# URC-ESP32.net
KiCad netlist of a schematic drawn in EAGLE
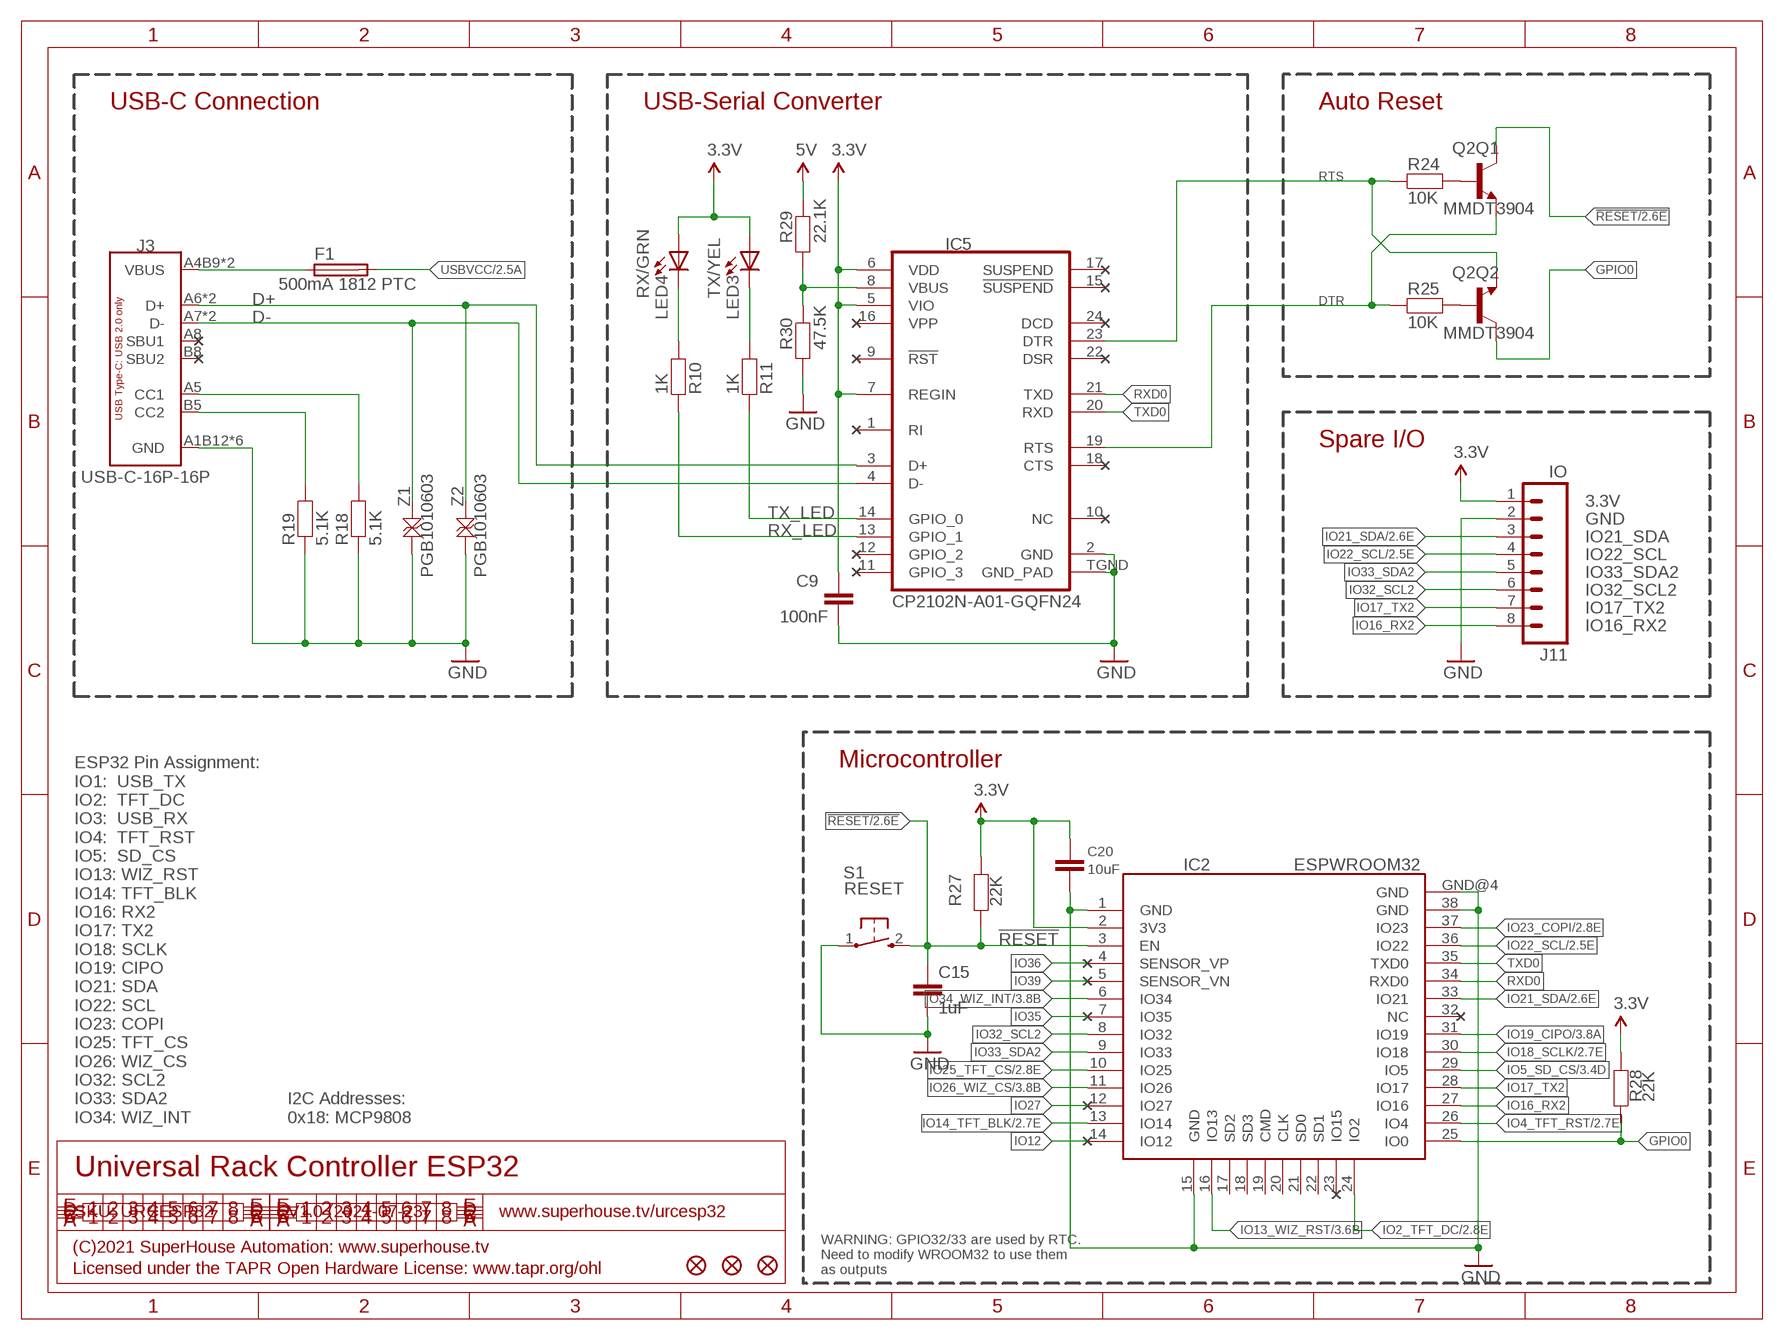
[diagram p0: schematic, sheet 1]
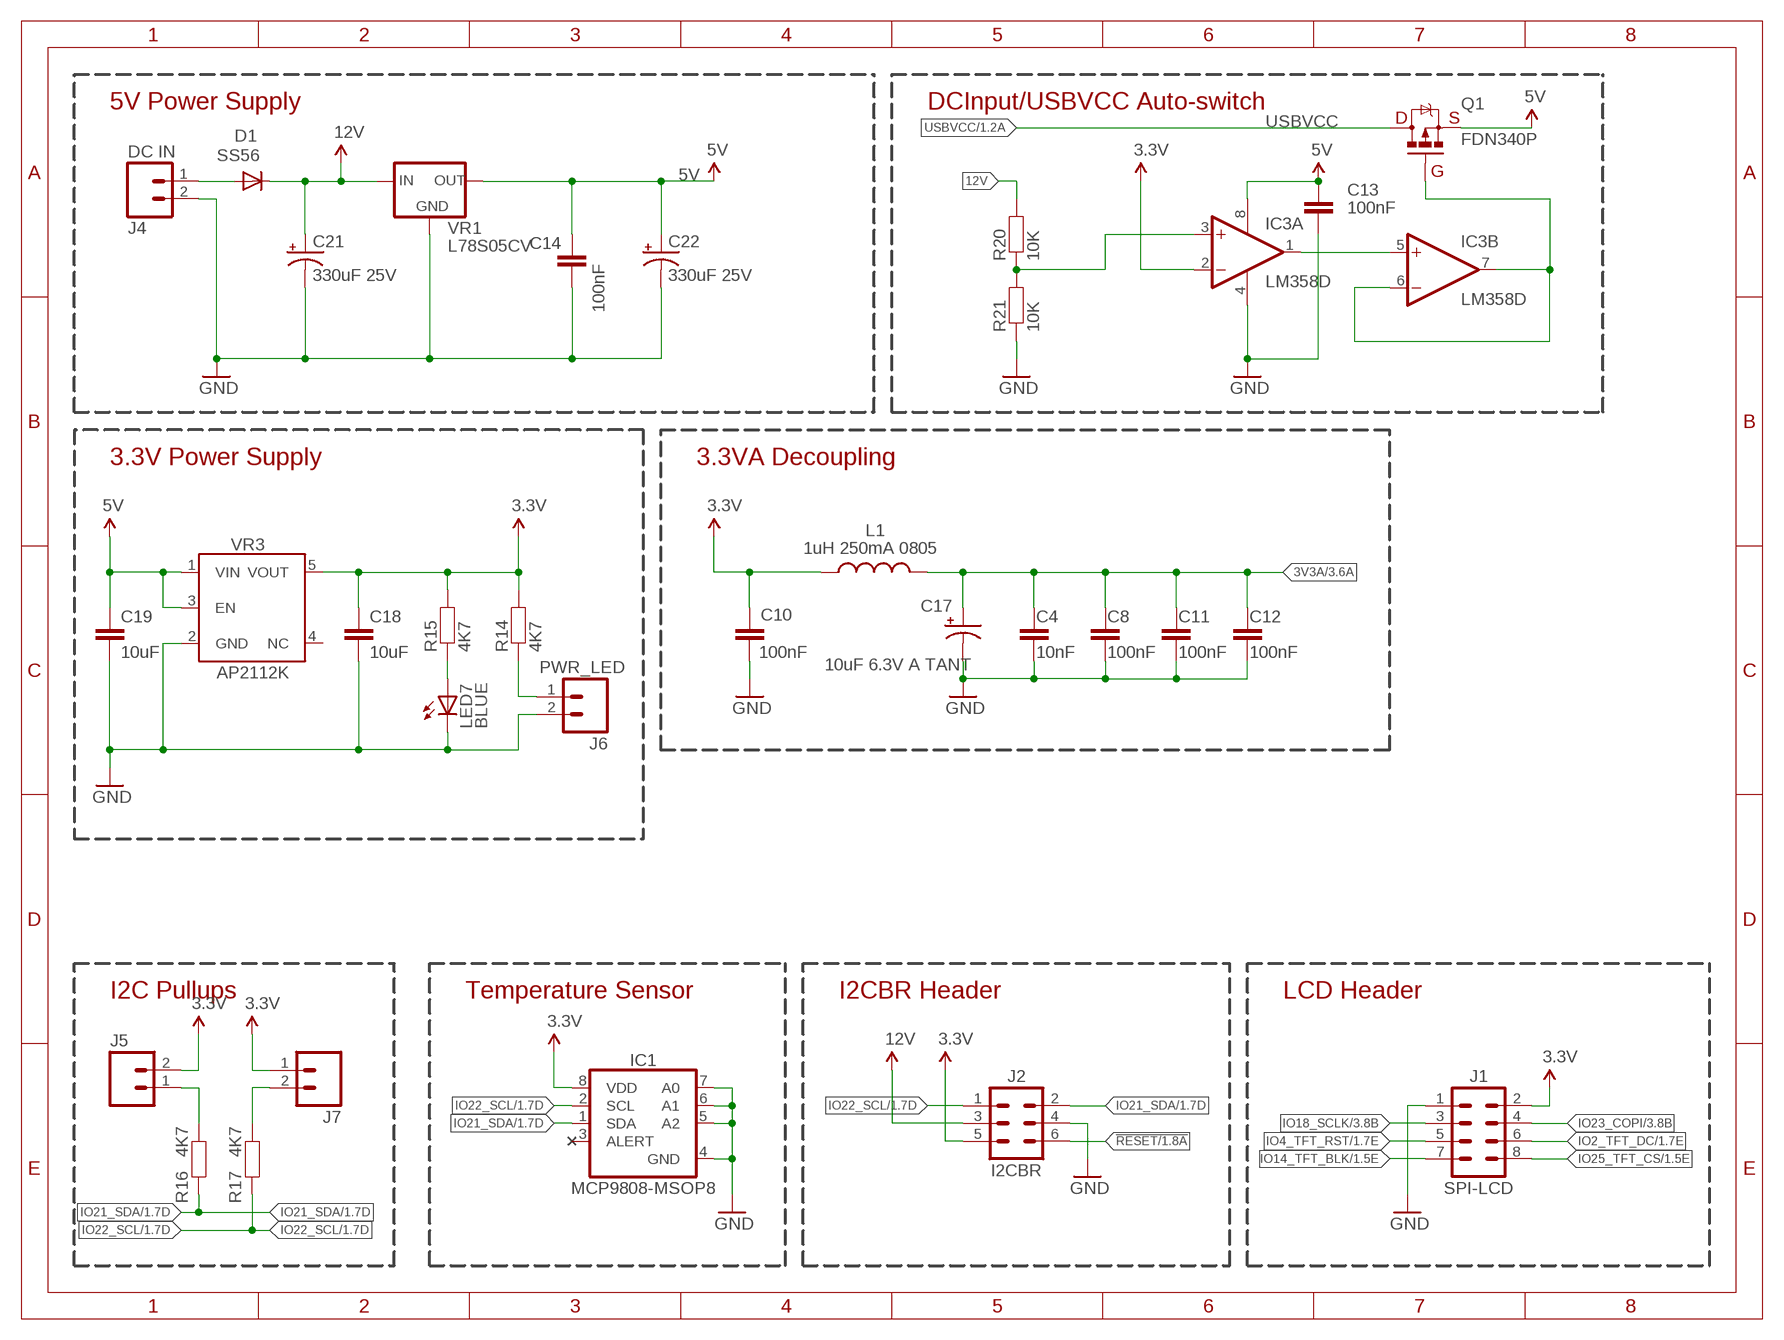
[diagram p1: schematic, sheet 2]
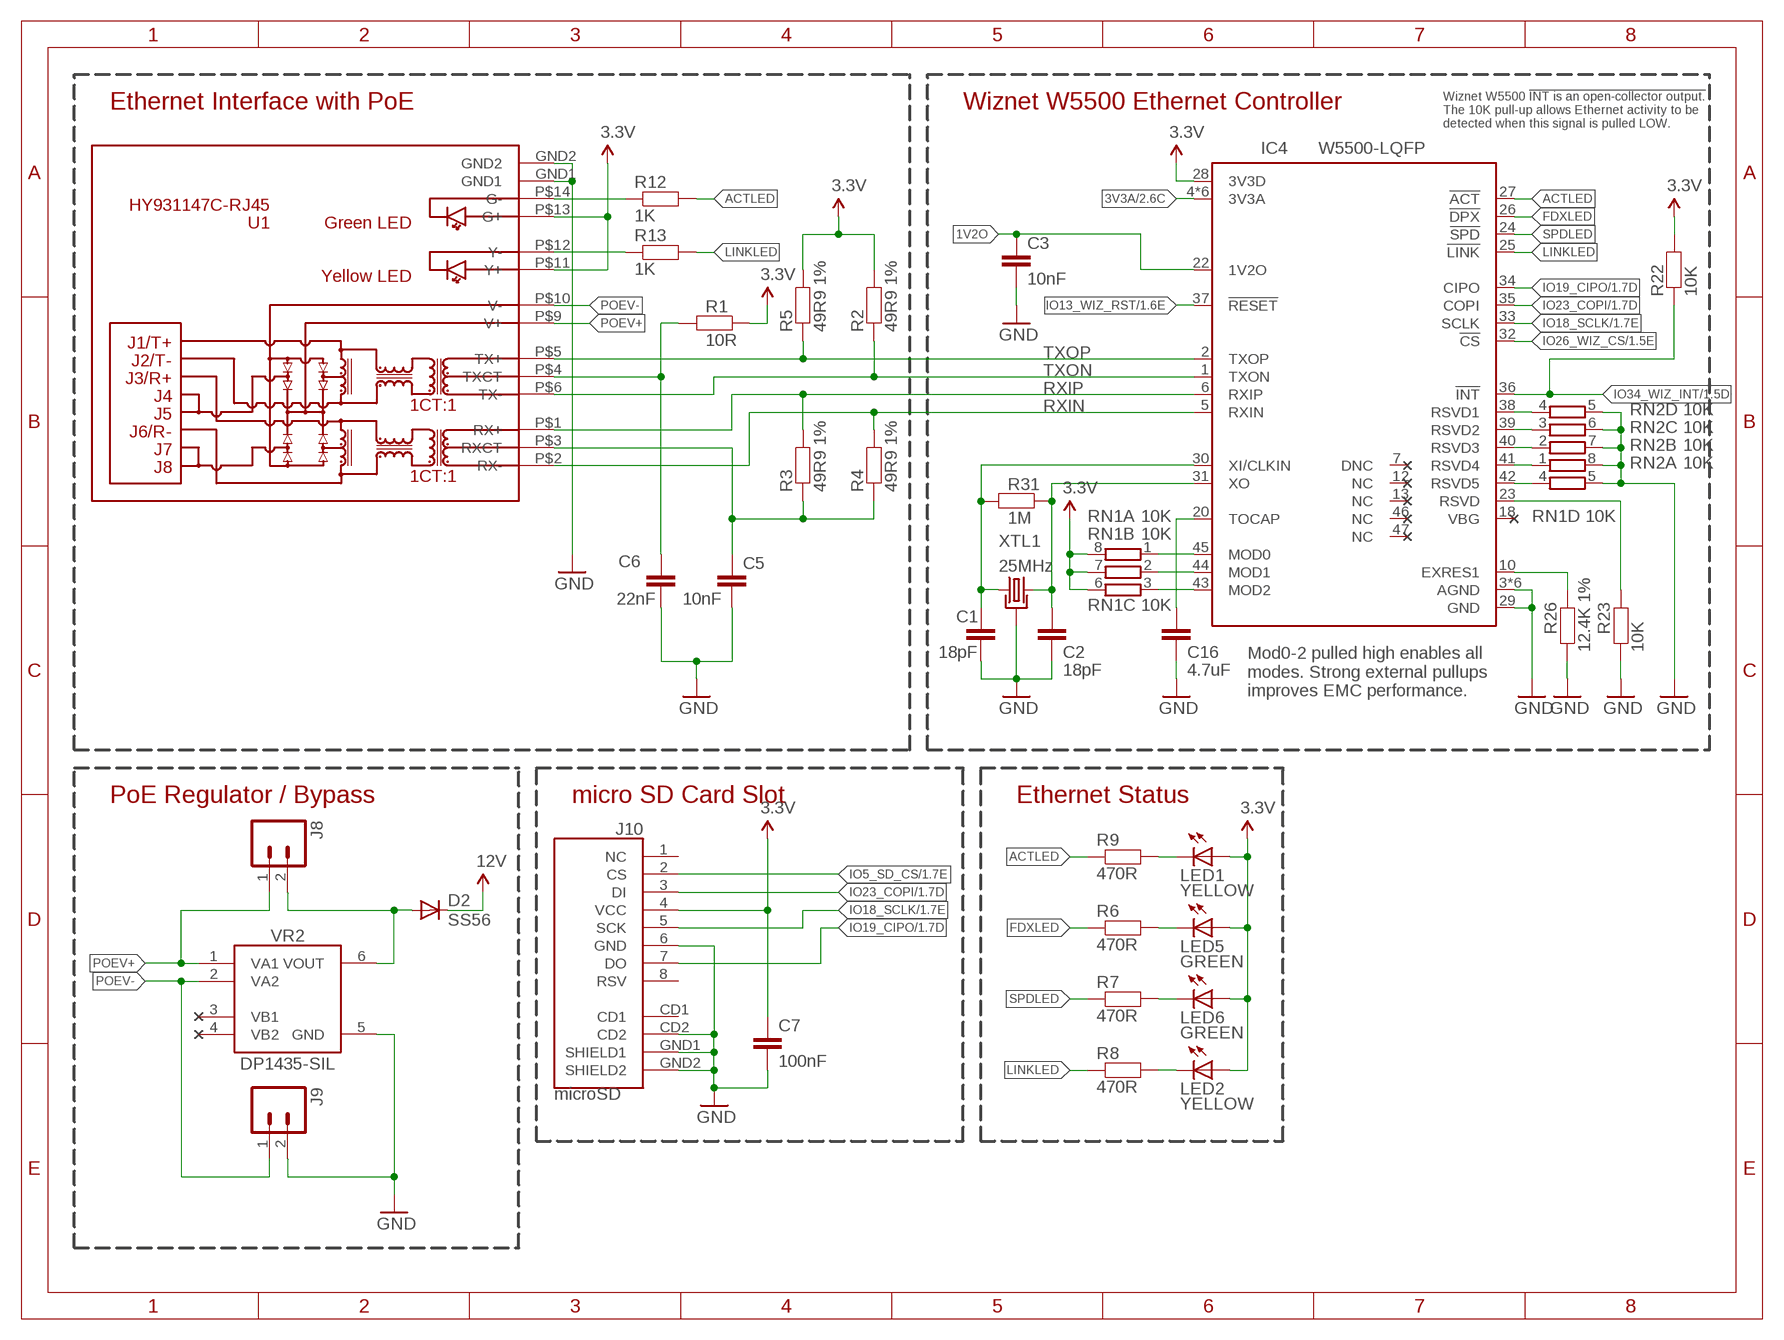
[diagram p2: schematic, sheet 3]

(export (version "E")
  (design (tool "Eeschema 10.0.6"))
  (components
    (comp (ref "C9")
      (value "100nF")
      (footprint "eagle-import:C0603")
      (libsource (lib "eagle-import") (part "CAP0603"))
    )
    (comp (ref "C15")
      (value "1uF")
      (footprint "eagle-import:C0603")
      (libsource (lib "eagle-import") (part "CAP0603"))
    )
    (comp (ref "C20")
      (value "10uF")
      (footprint "eagle-import:C0805")
      (libsource (lib "eagle-import") (part "CAP0805"))
    )
    (comp (ref "F1")
      (value "500mA 1812 PTC")
      (footprint "eagle-import:1812")
      (libsource (lib "eagle-import") (part "PTC-1812050"))
    )
    (comp (ref "FID1")
      (value "FIDUCIAL1X2.5")
      (footprint "eagle-import:FIDUCIAL-1X2.5")
      (libsource (lib "eagle-import") (part "FIDUCIAL1X2.5"))
    )
    (comp (ref "FID2")
      (value "FIDUCIAL1X2.5")
      (footprint "eagle-import:FIDUCIAL-1X2.5")
      (libsource (lib "eagle-import") (part "FIDUCIAL1X2.5"))
    )
    (comp (ref "FID3")
      (value "FIDUCIAL1X2.5")
      (footprint "eagle-import:FIDUCIAL-1X2.5")
      (libsource (lib "eagle-import") (part "FIDUCIAL1X2.5"))
    )
    (comp (ref "IC2")
      (value "ESPWROOM32")
      (footprint "eagle-import:ESPWROOM32")
      (libsource (lib "eagle-import") (part "ESPWROOM32"))
    )
    (comp (ref "IC5")
      (value "CP2102N-A01-GQFN24")
      (footprint "eagle-import:QFN-24")
      (libsource (lib "eagle-import") (part "CP2104"))
    )
    (comp (ref "J3")
      (value "USB-C-16P-16P")
      (footprint "eagle-import:USB-C-16P")
      (libsource (lib "eagle-import") (part "USB-C-16P-16P"))
    )
    (comp (ref "J11")
      (value "IO")
      (footprint "eagle-import:1X08")
      (libsource (lib "eagle-import") (part "M08-PLAIN"))
    )
    (comp (ref "LED3")
      (value "TX/YEL")
      (footprint "eagle-import:LED-0603")
      (libsource (lib "eagle-import") (part "LED0603"))
    )
    (comp (ref "LED4")
      (value "RX/GRN")
      (footprint "eagle-import:LED-0603")
      (libsource (lib "eagle-import") (part "LED0603"))
    )
    (comp (ref "Q2")
      (value "MMDT3904")
      (footprint "eagle-import:SOT-363")
      (libsource (lib "eagle-import") (part "TRANS_NPN_DUAL-MMDT3904"))
    )
    (comp (ref "R10")
      (value "1K")
      (footprint "eagle-import:R0603")
      (libsource (lib "eagle-import") (part "RESISTOR0603"))
    )
    (comp (ref "R11")
      (value "1K")
      (footprint "eagle-import:R0603")
      (libsource (lib "eagle-import") (part "RESISTOR0603"))
    )
    (comp (ref "R18")
      (value "5.1K")
      (footprint "eagle-import:R0603")
      (libsource (lib "eagle-import") (part "RESISTOR0603"))
    )
    (comp (ref "R19")
      (value "5.1K")
      (footprint "eagle-import:R0603")
      (libsource (lib "eagle-import") (part "RESISTOR0603"))
    )
    (comp (ref "R24")
      (value "10K")
      (footprint "eagle-import:R0603")
      (libsource (lib "eagle-import") (part "RESISTOR0603"))
    )
    (comp (ref "R25")
      (value "10K")
      (footprint "eagle-import:R0603")
      (libsource (lib "eagle-import") (part "RESISTOR0603"))
    )
    (comp (ref "R27")
      (value "22K")
      (footprint "eagle-import:R0603")
      (libsource (lib "eagle-import") (part "RESISTOR0603"))
    )
    (comp (ref "R28")
      (value "22K")
      (footprint "eagle-import:R0603")
      (libsource (lib "eagle-import") (part "RESISTOR0603"))
    )
    (comp (ref "R29")
      (value "22.1K")
      (footprint "eagle-import:R0603")
      (libsource (lib "eagle-import") (part "RESISTOR0603"))
    )
    (comp (ref "R30")
      (value "47.5K")
      (footprint "eagle-import:R0603")
      (libsource (lib "eagle-import") (part "RESISTOR0603"))
    )
    (comp (ref "S1")
      (value "RESET")
      (footprint "eagle-import:TACTILE_SMT_3X4X2")
      (libsource (lib "eagle-import") (part "TAC_SWITCH_2PINSMT"))
    )
    (comp (ref "Z1")
      (value "PGB1010603")
      (footprint "eagle-import:TVS0603")
      (libsource (lib "eagle-import") (part "TVS0603"))
    )
    (comp (ref "Z2")
      (value "PGB1010603")
      (footprint "eagle-import:TVS0603")
      (libsource (lib "eagle-import") (part "TVS0603"))
    )
    (comp (ref "C1")
      (value "18pF")
      (footprint "eagle-import:C0603")
      (libsource (lib "eagle-import") (part "CAP0603"))
    )
    (comp (ref "C2")
      (value "18pF")
      (footprint "eagle-import:C0603")
      (libsource (lib "eagle-import") (part "CAP0603"))
    )
    (comp (ref "C3")
      (value "10nF")
      (footprint "eagle-import:C0603")
      (libsource (lib "eagle-import") (part "CAP0603"))
    )
    (comp (ref "C5")
      (value "10nF")
      (footprint "eagle-import:C0603")
      (libsource (lib "eagle-import") (part "CAP0603"))
    )
    (comp (ref "C6")
      (value "22nF")
      (footprint "eagle-import:C0603")
      (libsource (lib "eagle-import") (part "CAP0603"))
    )
    (comp (ref "C7")
      (value "100nF")
      (footprint "eagle-import:C0603")
      (libsource (lib "eagle-import") (part "CAP0603"))
    )
    (comp (ref "C16")
      (value "4.7uF")
      (footprint "eagle-import:C0603")
      (libsource (lib "eagle-import") (part "CAP0603"))
    )
    (comp (ref "D2")
      (value "SS56")
      (footprint "eagle-import:SMA-DIODE")
      (libsource (lib "eagle-import") (part "DIODESMA"))
    )
    (comp (ref "IC4")
      (value "W5500-LQFP")
      (footprint "eagle-import:LQFP48")
      (libsource (lib "eagle-import") (part "W5500-LQFP"))
    )
    (comp (ref "J8")
      (value "M02-PIN-JUMP-Y")
      (footprint "eagle-import:1X02-P-JUMP-Y")
      (libsource (lib "eagle-import") (part "M02-PIN-JUMP-Y"))
    )
    (comp (ref "J9")
      (value "M02-PIN-JUMP-Y")
      (footprint "eagle-import:1X02-P-JUMP-Y")
      (libsource (lib "eagle-import") (part "M02-PIN-JUMP-Y"))
    )
    (comp (ref "J10")
      (value "microSD")
      (footprint "eagle-import:MICRO-SD-SOCKET-PP")
      (libsource (lib "eagle-import") (part "USD-SOCKETNEW"))
    )
    (comp (ref "LED1")
      (value "YELLOW")
      (footprint "eagle-import:LED-0603")
      (libsource (lib "eagle-import") (part "LED0603"))
    )
    (comp (ref "LED2")
      (value "YELLOW")
      (footprint "eagle-import:LED-0603")
      (libsource (lib "eagle-import") (part "LED0603"))
    )
    (comp (ref "LED5")
      (value "GREEN")
      (footprint "eagle-import:LED-0603")
      (libsource (lib "eagle-import") (part "LED0603"))
    )
    (comp (ref "LED6")
      (value "GREEN")
      (footprint "eagle-import:LED-0603")
      (libsource (lib "eagle-import") (part "LED0603"))
    )
    (comp (ref "R1")
      (value "10R")
      (footprint "eagle-import:R0603")
      (libsource (lib "eagle-import") (part "RESISTOR0603"))
    )
    (comp (ref "R2")
      (value "49R9 1%")
      (footprint "eagle-import:R0603")
      (libsource (lib "eagle-import") (part "RESISTOR0603"))
    )
    (comp (ref "R3")
      (value "49R9 1%")
      (footprint "eagle-import:R0603")
      (libsource (lib "eagle-import") (part "RESISTOR0603"))
    )
    (comp (ref "R4")
      (value "49R9 1%")
      (footprint "eagle-import:R0603")
      (libsource (lib "eagle-import") (part "RESISTOR0603"))
    )
    (comp (ref "R5")
      (value "49R9 1%")
      (footprint "eagle-import:R0603")
      (libsource (lib "eagle-import") (part "RESISTOR0603"))
    )
    (comp (ref "R6")
      (value "470R")
      (footprint "eagle-import:R0603")
      (libsource (lib "eagle-import") (part "RESISTOR0603"))
    )
    (comp (ref "R7")
      (value "470R")
      (footprint "eagle-import:R0603")
      (libsource (lib "eagle-import") (part "RESISTOR0603"))
    )
    (comp (ref "R8")
      (value "470R")
      (footprint "eagle-import:R0603")
      (libsource (lib "eagle-import") (part "RESISTOR0603"))
    )
    (comp (ref "R9")
      (value "470R")
      (footprint "eagle-import:R0603")
      (libsource (lib "eagle-import") (part "RESISTOR0603"))
    )
    (comp (ref "R12")
      (value "1K")
      (footprint "eagle-import:R0603")
      (libsource (lib "eagle-import") (part "RESISTOR0603"))
    )
    (comp (ref "R13")
      (value "1K")
      (footprint "eagle-import:R0603")
      (libsource (lib "eagle-import") (part "RESISTOR0603"))
    )
    (comp (ref "R22")
      (value "10K")
      (footprint "eagle-import:R0603")
      (libsource (lib "eagle-import") (part "RESISTOR0603"))
    )
    (comp (ref "R23")
      (value "10K")
      (footprint "eagle-import:R0603")
      (libsource (lib "eagle-import") (part "RESISTOR0603"))
    )
    (comp (ref "R26")
      (value "12.4K 1%")
      (footprint "eagle-import:R0603")
      (libsource (lib "eagle-import") (part "RESISTOR0603"))
    )
    (comp (ref "R31")
      (value "1M")
      (footprint "eagle-import:R0603")
      (libsource (lib "eagle-import") (part "RESISTOR0603"))
    )
    (comp (ref "RN1")
      (value "10K")
      (footprint "eagle-import:CAY16")
      (libsource (lib "eagle-import") (part "4R-NCAY16"))
    )
    (comp (ref "RN2")
      (value "10K")
      (footprint "eagle-import:CAY16")
      (libsource (lib "eagle-import") (part "4R-NCAY16"))
    )
    (comp (ref "U1")
      (value "HY931147C-RJ45")
      (footprint "eagle-import:HY931147C")
      (libsource (lib "eagle-import") (part "HY931147C-RJ45"))
    )
    (comp (ref "VR2")
      (value "DP1435-SIL")
      (footprint "eagle-import:DP1435")
      (libsource (lib "eagle-import") (part "DP1435-SIL"))
    )
    (comp (ref "XTL1")
      (value "25MHz")
      (footprint "eagle-import:CRYSTAL-SMD-3X2")
      (libsource (lib "eagle-import") (part "CRYSTAL-GND3X2"))
    )
    (comp (ref "C4")
      (value "10nF")
      (footprint "eagle-import:C0603")
      (libsource (lib "eagle-import") (part "CAP0603"))
    )
    (comp (ref "C8")
      (value "100nF")
      (footprint "eagle-import:C0603")
      (libsource (lib "eagle-import") (part "CAP0603"))
    )
    (comp (ref "C10")
      (value "100nF")
      (footprint "eagle-import:C0603")
      (libsource (lib "eagle-import") (part "CAP0603"))
    )
    (comp (ref "C11")
      (value "100nF")
      (footprint "eagle-import:C0603")
      (libsource (lib "eagle-import") (part "CAP0603"))
    )
    (comp (ref "C12")
      (value "100nF")
      (footprint "eagle-import:C0603")
      (libsource (lib "eagle-import") (part "CAP0603"))
    )
    (comp (ref "C13")
      (value "100nF")
      (footprint "eagle-import:C0603")
      (libsource (lib "eagle-import") (part "CAP0603"))
    )
    (comp (ref "C14")
      (value "100nF")
      (footprint "eagle-import:C0603")
      (libsource (lib "eagle-import") (part "CAP0603"))
    )
    (comp (ref "C17")
      (value "10uF 6.3V A TANT")
      (footprint "eagle-import:EIA3216")
      (libsource (lib "eagle-import") (part "CAP_POL1206"))
    )
    (comp (ref "C18")
      (value "10uF")
      (footprint "eagle-import:C0805")
      (libsource (lib "eagle-import") (part "CAP0805"))
    )
    (comp (ref "C19")
      (value "10uF")
      (footprint "eagle-import:C0805")
      (libsource (lib "eagle-import") (part "CAP0805"))
    )
    (comp (ref "C21")
      (value "330uF 25V")
      (footprint "eagle-import:PANASONIC_G")
      (libsource (lib "eagle-import") (part "CAP_POLG"))
    )
    (comp (ref "C22")
      (value "330uF 25V")
      (footprint "eagle-import:PANASONIC_G")
      (libsource (lib "eagle-import") (part "CAP_POLG"))
    )
    (comp (ref "D1")
      (value "SS56")
      (footprint "eagle-import:SMA-DIODE")
      (libsource (lib "eagle-import") (part "DIODESMA"))
    )
    (comp (ref "IC1")
      (value "MCP9808-MSOP8")
      (footprint "eagle-import:MSOP-8")
      (libsource (lib "eagle-import") (part "MCP9808-MSOP8"))
    )
    (comp (ref "IC3")
      (value "LM358D")
      (footprint "eagle-import:SO08")
      (libsource (lib "eagle-import") (part "LM358D"))
    )
    (comp (ref "J1")
      (value "SPI-LCD")
      (footprint "eagle-import:2X04-2.54-SHROUDED")
      (libsource (lib "eagle-import") (part "M02X4-SHROUD"))
    )
    (comp (ref "J2")
      (value "I2CBR")
      (footprint "eagle-import:2X3-2.54-SHROUDED")
      (libsource (lib "eagle-import") (part "M02X3-SHROUDED"))
    )
    (comp (ref "J4")
      (value "DC IN")
      (footprint "eagle-import:SCREWTERMINAL-3.81MM-HOR-2")
      (libsource (lib "eagle-import") (part "M02-SCREW-3.81MM-HOR"))
    )
    (comp (ref "J5")
      (value "M02-PIN-JUMP-Y")
      (footprint "eagle-import:1X02-P-JUMP-Y")
      (libsource (lib "eagle-import") (part "M02-PIN-JUMP-Y"))
    )
    (comp (ref "J6")
      (value "PWR_LED")
      (footprint "eagle-import:1X02-KF2510")
      (libsource (lib "eagle-import") (part "M02-KF2510"))
    )
    (comp (ref "J7")
      (value "M02-PIN-JUMP-Y")
      (footprint "eagle-import:1X02-P-JUMP-Y")
      (libsource (lib "eagle-import") (part "M02-PIN-JUMP-Y"))
    )
    (comp (ref "L1")
      (value "1uH 250mA 0805")
      (footprint "eagle-import:L2012C")
      (libsource (lib "eagle-import") (part "L-USL2012C"))
    )
    (comp (ref "LED7")
      (value "BLUE")
      (footprint "eagle-import:LED-0603")
      (libsource (lib "eagle-import") (part "LED0603"))
    )
    (comp (ref "Q1")
      (value "FDN340P")
      (footprint "eagle-import:SOT23-3")
      (libsource (lib "eagle-import") (part "MOSFET-PCHANNEL-SMT"))
    )
    (comp (ref "R14")
      (value "4K7")
      (footprint "eagle-import:R0603")
      (libsource (lib "eagle-import") (part "RESISTOR0603"))
    )
    (comp (ref "R15")
      (value "4K7")
      (footprint "eagle-import:R0603")
      (libsource (lib "eagle-import") (part "RESISTOR0603"))
    )
    (comp (ref "R16")
      (value "4K7")
      (footprint "eagle-import:R0603")
      (libsource (lib "eagle-import") (part "RESISTOR0603"))
    )
    (comp (ref "R17")
      (value "4K7")
      (footprint "eagle-import:R0603")
      (libsource (lib "eagle-import") (part "RESISTOR0603"))
    )
    (comp (ref "R20")
      (value "10K")
      (footprint "eagle-import:R0603")
      (libsource (lib "eagle-import") (part "RESISTOR0603"))
    )
    (comp (ref "R21")
      (value "10K")
      (footprint "eagle-import:R0603")
      (libsource (lib "eagle-import") (part "RESISTOR0603"))
    )
    (comp (ref "VR1")
      (value "L78S05CV")
      (footprint "eagle-import:TO220")
      (libsource (lib "eagle-import") (part "78XX-L78XX-FLAT"))
    )
    (comp (ref "VR3")
      (value "AP2112KSOT25")
      (footprint "eagle-import:SOT23-5")
      (libsource (lib "eagle-import") (part "AP2112KSOT25"))
    )
  )
  (nets
    (net (code "1") (name "1V2O") (class "Default")
      (node (ref "C3") (pin "1") (pinfunction "1_1") (pintype "passive"))
      (node (ref "IC4") (pin "22") (pinfunction "1V2O_22") (pintype "passive"))
    )
    (net (code "2") (name "3.3V") (class "Default")
      (node (ref "C10") (pin "1") (pinfunction "1_1") (pintype "passive"))
      (node (ref "C18") (pin "1") (pinfunction "1_1") (pintype "passive"))
      (node (ref "C20") (pin "1") (pinfunction "1_1") (pintype "passive"))
      (node (ref "C7") (pin "1") (pinfunction "1_1") (pintype "passive"))
      (node (ref "C9") (pin "1") (pinfunction "1_1") (pintype "passive"))
      (node (ref "IC1") (pin "8") (pinfunction "VDD_8") (pintype "bidirectional"))
      (node (ref "IC2") (pin "2") (pinfunction "3V3_2") (pintype "power_in"))
      (node (ref "IC3") (pin "2") (pinfunction "-IN_2") (pintype "input"))
      (node (ref "IC4") (pin "28") (pinfunction "3V3D_28") (pintype "passive"))
      (node (ref "IC5") (pin "5") (pinfunction "VIO_5") (pintype "bidirectional"))
      (node (ref "IC5") (pin "6") (pinfunction "VDD_6") (pintype "power_in"))
      (node (ref "IC5") (pin "7") (pinfunction "REGIN_7") (pintype "power_in"))
      (node (ref "J1") (pin "2") (pinfunction "2_2") (pintype "passive"))
      (node (ref "J10") (pin "4") (pinfunction "VCC_4") (pintype "bidirectional"))
      (node (ref "J11") (pin "1") (pinfunction "1_1") (pintype "passive"))
      (node (ref "J2") (pin "5") (pinfunction "5_5") (pintype "passive"))
      (node (ref "J5") (pin "2") (pinfunction "2_2") (pintype "passive"))
      (node (ref "J7") (pin "1") (pinfunction "1_1") (pintype "passive"))
      (node (ref "L1") (pin "1") (pinfunction "1_1") (pintype "passive"))
      (node (ref "LED1") (pin "A") (pinfunction "A_A") (pintype "passive"))
      (node (ref "LED2") (pin "A") (pinfunction "A_A") (pintype "passive"))
      (node (ref "LED3") (pin "A") (pinfunction "A_A") (pintype "passive"))
      (node (ref "LED4") (pin "A") (pinfunction "A_A") (pintype "passive"))
      (node (ref "LED5") (pin "A") (pinfunction "A_A") (pintype "passive"))
      (node (ref "LED6") (pin "A") (pinfunction "A_A") (pintype "passive"))
      (node (ref "R1") (pin "1") (pinfunction "1_1") (pintype "passive"))
      (node (ref "R14") (pin "2") (pinfunction "2_2") (pintype "passive"))
      (node (ref "R15") (pin "2") (pinfunction "2_2") (pintype "passive"))
      (node (ref "R2") (pin "2") (pinfunction "2_2") (pintype "passive"))
      (node (ref "R22") (pin "2") (pinfunction "2_2") (pintype "passive"))
      (node (ref "R27") (pin "1") (pinfunction "1_1") (pintype "passive"))
      (node (ref "R28") (pin "1") (pinfunction "1_1") (pintype "passive"))
      (node (ref "R5") (pin "2") (pinfunction "2_2") (pintype "passive"))
      (node (ref "RN1") (pin "6") (pinfunction "2_6") (pintype "passive"))
      (node (ref "RN1") (pin "7") (pinfunction "2_7") (pintype "passive"))
      (node (ref "RN1") (pin "8") (pinfunction "2_8") (pintype "passive"))
      (node (ref "U1") (pin "P$11") (pinfunction "Y+_P$11") (pintype "bidirectional"))
      (node (ref "U1") (pin "P$13") (pinfunction "G+_P$13") (pintype "bidirectional"))
      (node (ref "VR3") (pin "5") (pinfunction "VOUT_5") (pintype "bidirectional"))
    )
    (net (code "3") (name "3V3A") (class "Default")
      (node (ref "C11") (pin "1") (pinfunction "1_1") (pintype "passive"))
      (node (ref "C12") (pin "1") (pinfunction "1_1") (pintype "passive"))
      (node (ref "C17") (pin "A") (pinfunction "+_A") (pintype "passive"))
      (node (ref "C4") (pin "1") (pinfunction "1_1") (pintype "passive"))
      (node (ref "C8") (pin "1") (pinfunction "1_1") (pintype "passive"))
      (node (ref "IC4") (pin "11") (pinfunction "3V3A_11") (pintype "passive"))
      (node (ref "IC4") (pin "15") (pinfunction "3V3A_15") (pintype "passive"))
      (node (ref "IC4") (pin "17") (pinfunction "3V3A_17") (pintype "passive"))
      (node (ref "IC4") (pin "21") (pinfunction "3V3A_21") (pintype "passive"))
      (node (ref "IC4") (pin "4") (pinfunction "3V3A_4") (pintype "passive"))
      (node (ref "IC4") (pin "8") (pinfunction "3V3A_8") (pintype "passive"))
      (node (ref "L1") (pin "2") (pinfunction "2_2") (pintype "passive"))
    )
    (net (code "4") (name "5V") (class "Default")
      (node (ref "C13") (pin "1") (pinfunction "1_1") (pintype "passive"))
      (node (ref "C14") (pin "1") (pinfunction "1_1") (pintype "passive"))
      (node (ref "C19") (pin "1") (pinfunction "1_1") (pintype "passive"))
      (node (ref "C22") (pin "+") (pinfunction "+_+") (pintype "passive"))
      (node (ref "IC3") (pin "8") (pinfunction "V+_8") (pintype "power_in"))
      (node (ref "Q1") (pin "2") (pinfunction "S_2") (pintype "passive"))
      (node (ref "R29") (pin "2") (pinfunction "2_2") (pintype "passive"))
      (node (ref "VR1") (pin "3") (pinfunction "OUT_3") (pintype "output"))
      (node (ref "VR3") (pin "1") (pinfunction "VIN_1") (pintype "bidirectional"))
      (node (ref "VR3") (pin "3") (pinfunction "EN_3") (pintype "bidirectional"))
    )
    (net (code "5") (name "12V") (class "Default")
      (node (ref "C21") (pin "+") (pinfunction "+_+") (pintype "passive"))
      (node (ref "D1") (pin "C") (pinfunction "C_C") (pintype "passive"))
      (node (ref "D2") (pin "C") (pinfunction "C_C") (pintype "passive"))
      (node (ref "J2") (pin "3") (pinfunction "3_3") (pintype "passive"))
      (node (ref "R20") (pin "2") (pinfunction "2_2") (pintype "passive"))
      (node (ref "VR1") (pin "1") (pinfunction "IN_1") (pintype "input"))
    )
    (net (code "6") (name "ACTLED") (class "Default")
      (node (ref "IC4") (pin "27") (pinfunction "~{ACT}_27") (pintype "passive"))
      (node (ref "R12") (pin "2") (pinfunction "2_2") (pintype "passive"))
      (node (ref "R9") (pin "1") (pinfunction "1_1") (pintype "passive"))
    )
    (net (code "7") (name "D+") (class "Default")
      (node (ref "IC5") (pin "3") (pinfunction "D+_3") (pintype "bidirectional"))
      (node (ref "J3") (pin "A6") (pinfunction "D+_A6") (pintype "bidirectional"))
      (node (ref "J3") (pin "B6") (pinfunction "D+_B6") (pintype "bidirectional"))
      (node (ref "Z2") (pin "2") (pinfunction "2_2") (pintype "passive"))
    )
    (net (code "8") (name "D-") (class "Default")
      (node (ref "IC5") (pin "4") (pinfunction "D-_4") (pintype "bidirectional"))
      (node (ref "J3") (pin "A7") (pinfunction "D-_A7") (pintype "bidirectional"))
      (node (ref "J3") (pin "B7") (pinfunction "D-_B7") (pintype "bidirectional"))
      (node (ref "Z1") (pin "2") (pinfunction "2_2") (pintype "passive"))
    )
    (net (code "9") (name "DTR") (class "Default")
      (node (ref "IC5") (pin "23") (pinfunction "DTR_23") (pintype "output"))
      (node (ref "Q2") (pin "1") (pinfunction "E_1") (pintype "passive"))
      (node (ref "R24") (pin "1") (pinfunction "1_1") (pintype "passive"))
    )
    (net (code "10") (name "FDXLED") (class "Default")
      (node (ref "IC4") (pin "26") (pinfunction "~{DPX}_26") (pintype "passive"))
      (node (ref "R6") (pin "1") (pinfunction "1_1") (pintype "passive"))
    )
    (net (code "11") (name "GND") (class "Default")
      (node (ref "C1") (pin "2") (pinfunction "2_2") (pintype "passive"))
      (node (ref "C10") (pin "2") (pinfunction "2_2") (pintype "passive"))
      (node (ref "C11") (pin "2") (pinfunction "2_2") (pintype "passive"))
      (node (ref "C12") (pin "2") (pinfunction "2_2") (pintype "passive"))
      (node (ref "C13") (pin "2") (pinfunction "2_2") (pintype "passive"))
      (node (ref "C14") (pin "2") (pinfunction "2_2") (pintype "passive"))
      (node (ref "C15") (pin "2") (pinfunction "2_2") (pintype "passive"))
      (node (ref "C16") (pin "2") (pinfunction "2_2") (pintype "passive"))
      (node (ref "C17") (pin "C") (pinfunction "-_C") (pintype "passive"))
      (node (ref "C18") (pin "2") (pinfunction "2_2") (pintype "passive"))
      (node (ref "C19") (pin "2") (pinfunction "2_2") (pintype "passive"))
      (node (ref "C2") (pin "2") (pinfunction "2_2") (pintype "passive"))
      (node (ref "C20") (pin "2") (pinfunction "2_2") (pintype "passive"))
      (node (ref "C21") (pin "-") (pinfunction "-_-") (pintype "passive"))
      (node (ref "C22") (pin "-") (pinfunction "-_-") (pintype "passive"))
      (node (ref "C3") (pin "2") (pinfunction "2_2") (pintype "passive"))
      (node (ref "C4") (pin "2") (pinfunction "2_2") (pintype "passive"))
      (node (ref "C5") (pin "2") (pinfunction "2_2") (pintype "passive"))
      (node (ref "C6") (pin "2") (pinfunction "2_2") (pintype "passive"))
      (node (ref "C7") (pin "2") (pinfunction "2_2") (pintype "passive"))
      (node (ref "C8") (pin "2") (pinfunction "2_2") (pintype "passive"))
      (node (ref "C9") (pin "2") (pinfunction "2_2") (pintype "passive"))
      (node (ref "IC1") (pin "4") (pinfunction "GND_4") (pintype "bidirectional"))
      (node (ref "IC1") (pin "5") (pinfunction "A2_5") (pintype "bidirectional"))
      (node (ref "IC1") (pin "6") (pinfunction "A1_6") (pintype "bidirectional"))
      (node (ref "IC1") (pin "7") (pinfunction "A0_7") (pintype "bidirectional"))
      (node (ref "IC2") (pin "1") (pinfunction "GND_1") (pintype "power_in"))
      (node (ref "IC2") (pin "15") (pinfunction "GND_15") (pintype "power_in"))
      (node (ref "IC2") (pin "38") (pinfunction "GND_38") (pintype "power_in"))
      (node (ref "IC2") (pin "GND@4") (pinfunction "GND_GND@4") (pintype "power_in"))
      (node (ref "IC3") (pin "4") (pinfunction "V-_4") (pintype "power_in"))
      (node (ref "IC4") (pin "14") (pinfunction "AGND_14") (pintype "passive"))
      (node (ref "IC4") (pin "16") (pinfunction "AGND_16") (pintype "passive"))
      (node (ref "IC4") (pin "19") (pinfunction "AGND_19") (pintype "passive"))
      (node (ref "IC4") (pin "29") (pinfunction "GND_29") (pintype "passive"))
      (node (ref "IC4") (pin "3") (pinfunction "AGND_3") (pintype "passive"))
      (node (ref "IC4") (pin "48") (pinfunction "AGND_48") (pintype "passive"))
      (node (ref "IC4") (pin "9") (pinfunction "AGND_9") (pintype "passive"))
      (node (ref "IC5") (pin "2") (pinfunction "GND_2") (pintype "power_in"))
      (node (ref "IC5") (pin "TGND") (pinfunction "GND_PAD_TGND") (pintype "power_in"))
      (node (ref "J1") (pin "1") (pinfunction "1_1") (pintype "passive"))
      (node (ref "J10") (pin "6") (pinfunction "GND_6") (pintype "bidirectional"))
      (node (ref "J10") (pin "CD2") (pinfunction "CD2_CD2") (pintype "bidirectional"))
      (node (ref "J10") (pin "GND1") (pinfunction "SHIELD1_GND1") (pintype "bidirectional"))
      (node (ref "J10") (pin "GND2") (pinfunction "SHIELD2_GND2") (pintype "bidirectional"))
      (node (ref "J11") (pin "2") (pinfunction "2_2") (pintype "passive"))
      (node (ref "J2") (pin "4") (pinfunction "4_4") (pintype "passive"))
      (node (ref "J3") (pin "A12B1") (pinfunction "GND_A12B1") (pintype "power_in"))
      (node (ref "J3") (pin "A1B12") (pinfunction "GND_A1B12") (pintype "power_in"))
      (node (ref "J3") (pin "FIX1") (pinfunction "GND_FIX1") (pintype "power_in"))
      (node (ref "J3") (pin "FIX2") (pinfunction "GND_FIX2") (pintype "power_in"))
      (node (ref "J3") (pin "FIX3") (pinfunction "GND_FIX3") (pintype "power_in"))
      (node (ref "J3") (pin "FIX4") (pinfunction "GND_FIX4") (pintype "power_in"))
      (node (ref "J4") (pin "2") (pinfunction "2_2") (pintype "passive"))
      (node (ref "J6") (pin "2") (pinfunction "2_2") (pintype "passive"))
      (node (ref "J9") (pin "2") (pinfunction "2_2") (pintype "passive"))
      (node (ref "LED7") (pin "C") (pinfunction "C_C") (pintype "passive"))
      (node (ref "R18") (pin "1") (pinfunction "1_1") (pintype "passive"))
      (node (ref "R19") (pin "1") (pinfunction "1_1") (pintype "passive"))
      (node (ref "R21") (pin "1") (pinfunction "1_1") (pintype "passive"))
      (node (ref "R23") (pin "2") (pinfunction "2_2") (pintype "passive"))
      (node (ref "R26") (pin "2") (pinfunction "2_2") (pintype "passive"))
      (node (ref "R30") (pin "1") (pinfunction "1_1") (pintype "passive"))
      (node (ref "RN1") (pin "5") (pinfunction "2_5") (pintype "passive"))
      (node (ref "RN2") (pin "5") (pinfunction "2_5") (pintype "passive"))
      (node (ref "RN2") (pin "6") (pinfunction "2_6") (pintype "passive"))
      (node (ref "RN2") (pin "7") (pinfunction "2_7") (pintype "passive"))
      (node (ref "RN2") (pin "8") (pinfunction "2_8") (pintype "passive"))
      (node (ref "S1") (pin "1") (pinfunction "P_1") (pintype "passive"))
      (node (ref "U1") (pin "GND1") (pinfunction "GND1_GND1") (pintype "bidirectional"))
      (node (ref "U1") (pin "GND2") (pinfunction "GND2_GND2") (pintype "bidirectional"))
      (node (ref "VR1") (pin "2") (pinfunction "GND_2") (pintype "input"))
      (node (ref "VR1") (pin "HEATSINK") (pinfunction "GND_HEATSINK") (pintype "input"))
      (node (ref "VR1") (pin "TAB") (pinfunction "GND_TAB") (pintype "input"))
      (node (ref "VR2") (pin "5") (pinfunction "GND_5") (pintype "bidirectional"))
      (node (ref "VR3") (pin "2") (pinfunction "GND_2") (pintype "bidirectional"))
      (node (ref "XTL1") (pin "2") (pinfunction "GND_2") (pintype "bidirectional"))
      (node (ref "XTL1") (pin "4") (pinfunction "GND_4") (pintype "bidirectional"))
      (node (ref "Z1") (pin "1") (pinfunction "1_1") (pintype "passive"))
      (node (ref "Z2") (pin "1") (pinfunction "1_1") (pintype "passive"))
    )
    (net (code "12") (name "GPIO0") (class "Default")
      (node (ref "IC2") (pin "25") (pinfunction "IO0_25") (pintype "bidirectional"))
      (node (ref "Q2") (pin "6") (pinfunction "C_6") (pintype "passive"))
      (node (ref "R28") (pin "2") (pinfunction "2_2") (pintype "passive"))
    )
    (net (code "13") (name "IO2_TFT_DC") (class "Default")
      (node (ref "IC2") (pin "24") (pinfunction "IO2_24") (pintype "bidirectional"))
      (node (ref "J1") (pin "6") (pinfunction "6_6") (pintype "passive"))
    )
    (net (code "14") (name "IO4_TFT_RST") (class "Default")
      (node (ref "IC2") (pin "26") (pinfunction "IO4_26") (pintype "bidirectional"))
      (node (ref "J1") (pin "5") (pinfunction "5_5") (pintype "passive"))
    )
    (net (code "15") (name "IO5_SD_CS") (class "Default")
      (node (ref "IC2") (pin "29") (pinfunction "IO5_29") (pintype "bidirectional"))
      (node (ref "J10") (pin "2") (pinfunction "CS_2") (pintype "bidirectional"))
    )
    (net (code "16") (name "IO12") (class "Default")
      (node (ref "IC2") (pin "14") (pinfunction "IO12_14") (pintype "bidirectional"))
    )
    (net (code "17") (name "IO13_WIZ_RST") (class "Default")
      (node (ref "IC2") (pin "16") (pinfunction "IO13_16") (pintype "bidirectional"))
      (node (ref "IC4") (pin "37") (pinfunction "~{RESET}_37") (pintype "passive"))
    )
    (net (code "18") (name "IO14_TFT_BLK") (class "Default")
      (node (ref "IC2") (pin "13") (pinfunction "IO14_13") (pintype "bidirectional"))
      (node (ref "J1") (pin "7") (pinfunction "7_7") (pintype "passive"))
    )
    (net (code "19") (name "IO16_RX2") (class "Default")
      (node (ref "IC2") (pin "27") (pinfunction "IO16_27") (pintype "bidirectional"))
      (node (ref "J11") (pin "8") (pinfunction "8_8") (pintype "passive"))
    )
    (net (code "20") (name "IO17_TX2") (class "Default")
      (node (ref "IC2") (pin "28") (pinfunction "IO17_28") (pintype "bidirectional"))
      (node (ref "J11") (pin "7") (pinfunction "7_7") (pintype "passive"))
    )
    (net (code "21") (name "IO18_SCLK") (class "Default")
      (node (ref "IC2") (pin "30") (pinfunction "IO18_30") (pintype "bidirectional"))
      (node (ref "IC4") (pin "33") (pinfunction "SCLK_33") (pintype "passive"))
      (node (ref "J1") (pin "3") (pinfunction "3_3") (pintype "passive"))
      (node (ref "J10") (pin "5") (pinfunction "SCK_5") (pintype "bidirectional"))
    )
    (net (code "22") (name "IO19_CIPO") (class "Default")
      (node (ref "IC2") (pin "31") (pinfunction "IO19_31") (pintype "bidirectional"))
      (node (ref "IC4") (pin "34") (pinfunction "CIPO_34") (pintype "passive"))
      (node (ref "J10") (pin "7") (pinfunction "DO_7") (pintype "bidirectional"))
    )
    (net (code "23") (name "IO21_SDA") (class "Default")
      (node (ref "IC1") (pin "1") (pinfunction "SDA_1") (pintype "bidirectional"))
      (node (ref "IC2") (pin "33") (pinfunction "IO21_33") (pintype "bidirectional"))
      (node (ref "J11") (pin "3") (pinfunction "3_3") (pintype "passive"))
      (node (ref "J2") (pin "2") (pinfunction "2_2") (pintype "passive"))
      (node (ref "R16") (pin "2") (pinfunction "2_2") (pintype "passive"))
    )
    (net (code "24") (name "IO22_SCL") (class "Default")
      (node (ref "IC1") (pin "2") (pinfunction "SCL_2") (pintype "bidirectional"))
      (node (ref "IC2") (pin "36") (pinfunction "IO22_36") (pintype "bidirectional"))
      (node (ref "J11") (pin "4") (pinfunction "4_4") (pintype "passive"))
      (node (ref "J2") (pin "1") (pinfunction "1_1") (pintype "passive"))
      (node (ref "R17") (pin "2") (pinfunction "2_2") (pintype "passive"))
    )
    (net (code "25") (name "IO23_COPI") (class "Default")
      (node (ref "IC2") (pin "37") (pinfunction "IO23_37") (pintype "bidirectional"))
      (node (ref "IC4") (pin "35") (pinfunction "COPI_35") (pintype "passive"))
      (node (ref "J1") (pin "4") (pinfunction "4_4") (pintype "passive"))
      (node (ref "J10") (pin "3") (pinfunction "DI_3") (pintype "bidirectional"))
    )
    (net (code "26") (name "IO25_TFT_CS") (class "Default")
      (node (ref "IC2") (pin "10") (pinfunction "IO25_10") (pintype "bidirectional"))
      (node (ref "J1") (pin "8") (pinfunction "8_8") (pintype "passive"))
    )
    (net (code "27") (name "IO26_WIZ_CS") (class "Default")
      (node (ref "IC2") (pin "11") (pinfunction "IO26_11") (pintype "bidirectional"))
      (node (ref "IC4") (pin "32") (pinfunction "~{CS}_32") (pintype "passive"))
    )
    (net (code "28") (name "IO27") (class "Default")
      (node (ref "IC2") (pin "12") (pinfunction "IO27_12") (pintype "bidirectional"))
    )
    (net (code "29") (name "IO32_SCL2") (class "Default")
      (node (ref "IC2") (pin "8") (pinfunction "IO32_8") (pintype "bidirectional"))
      (node (ref "J11") (pin "6") (pinfunction "6_6") (pintype "passive"))
    )
    (net (code "30") (name "IO33_SDA2") (class "Default")
      (node (ref "IC2") (pin "9") (pinfunction "IO33_9") (pintype "bidirectional"))
      (node (ref "J11") (pin "5") (pinfunction "5_5") (pintype "passive"))
    )
    (net (code "31") (name "IO34_WIZ_INT") (class "Default")
      (node (ref "IC2") (pin "6") (pinfunction "IO34_6") (pintype "bidirectional"))
      (node (ref "IC4") (pin "36") (pinfunction "~{INT}_36") (pintype "passive"))
      (node (ref "R22") (pin "1") (pinfunction "1_1") (pintype "passive"))
    )
    (net (code "32") (name "IO35") (class "Default")
      (node (ref "IC2") (pin "7") (pinfunction "IO35_7") (pintype "bidirectional"))
    )
    (net (code "33") (name "IO36") (class "Default")
      (node (ref "IC2") (pin "4") (pinfunction "SENSOR_VP_4") (pintype "bidirectional"))
    )
    (net (code "34") (name "IO39") (class "Default")
      (node (ref "IC2") (pin "5") (pinfunction "SENSOR_VN_5") (pintype "bidirectional"))
    )
    (net (code "35") (name "LINKLED") (class "Default")
      (node (ref "IC4") (pin "25") (pinfunction "~{LINK}_25") (pintype "passive"))
      (node (ref "R13") (pin "2") (pinfunction "2_2") (pintype "passive"))
      (node (ref "R8") (pin "1") (pinfunction "1_1") (pintype "passive"))
    )
    (net (code "36") (name "Net-(D1-PadA)") (class "Default")
      (node (ref "D1") (pin "A") (pinfunction "A_A") (pintype "passive"))
      (node (ref "J4") (pin "1") (pinfunction "1_1") (pintype "passive"))
    )
    (net (code "37") (name "Net-(F1-Pad1)") (class "Default")
      (node (ref "F1") (pin "1") (pinfunction "1_1") (pintype "passive"))
      (node (ref "J3") (pin "A4B9") (pinfunction "VBUS_A4B9") (pintype "power_in"))
      (node (ref "J3") (pin "A9B4") (pinfunction "VBUS_A9B4") (pintype "power_in"))
    )
    (net (code "38") (name "Net-(IC3A-+IN)") (class "Default")
      (node (ref "IC3") (pin "3") (pinfunction "+IN_3") (pintype "input"))
      (node (ref "R20") (pin "1") (pinfunction "1_1") (pintype "passive"))
      (node (ref "R21") (pin "2") (pinfunction "2_2") (pintype "passive"))
    )
    (net (code "39") (name "Net-(IC3A-OUT)") (class "Default")
      (node (ref "IC3") (pin "1") (pinfunction "OUT_1") (pintype "output"))
      (node (ref "IC3") (pin "5") (pinfunction "+IN_5") (pintype "input"))
    )
    (net (code "40") (name "Net-(IC3B--IN)") (class "Default")
      (node (ref "IC3") (pin "6") (pinfunction "-IN_6") (pintype "input"))
      (node (ref "IC3") (pin "7") (pinfunction "OUT_7") (pintype "output"))
      (node (ref "Q1") (pin "1") (pinfunction "G_1") (pintype "passive"))
    )
    (net (code "41") (name "Net-(IC4-EXRES1)") (class "Default")
      (node (ref "IC4") (pin "10") (pinfunction "EXRES1_10") (pintype "passive"))
      (node (ref "R26") (pin "1") (pinfunction "1_1") (pintype "passive"))
    )
    (net (code "42") (name "Net-(IC4-MOD0)") (class "Default")
      (node (ref "IC4") (pin "45") (pinfunction "MOD0_45") (pintype "passive"))
      (node (ref "RN1") (pin "1") (pinfunction "1_1") (pintype "passive"))
    )
    (net (code "43") (name "Net-(IC4-MOD1)") (class "Default")
      (node (ref "IC4") (pin "44") (pinfunction "MOD1_44") (pintype "passive"))
      (node (ref "RN1") (pin "2") (pinfunction "1_2") (pintype "passive"))
    )
    (net (code "44") (name "Net-(IC4-MOD2)") (class "Default")
      (node (ref "IC4") (pin "43") (pinfunction "MOD2_43") (pintype "passive"))
      (node (ref "RN1") (pin "3") (pinfunction "1_3") (pintype "passive"))
    )
    (net (code "45") (name "Net-(IC4-RSVD)") (class "Default")
      (node (ref "IC4") (pin "23") (pinfunction "RSVD_23") (pintype "passive"))
      (node (ref "R23") (pin "1") (pinfunction "1_1") (pintype "passive"))
    )
    (net (code "46") (name "Net-(IC4-RSVD1)") (class "Default")
      (node (ref "IC4") (pin "38") (pinfunction "RSVD1_38") (pintype "passive"))
      (node (ref "RN2") (pin "4") (pinfunction "1_4") (pintype "passive"))
    )
    (net (code "47") (name "Net-(IC4-RSVD2)") (class "Default")
      (node (ref "IC4") (pin "39") (pinfunction "RSVD2_39") (pintype "passive"))
      (node (ref "RN2") (pin "3") (pinfunction "1_3") (pintype "passive"))
    )
    (net (code "48") (name "Net-(IC4-RSVD3)") (class "Default")
      (node (ref "IC4") (pin "40") (pinfunction "RSVD3_40") (pintype "passive"))
      (node (ref "RN2") (pin "2") (pinfunction "1_2") (pintype "passive"))
    )
    (net (code "49") (name "Net-(IC4-RSVD4)") (class "Default")
      (node (ref "IC4") (pin "41") (pinfunction "RSVD4_41") (pintype "passive"))
      (node (ref "RN2") (pin "1") (pinfunction "1_1") (pintype "passive"))
    )
    (net (code "50") (name "Net-(IC4-RSVD5)") (class "Default")
      (node (ref "IC4") (pin "42") (pinfunction "RSVD5_42") (pintype "passive"))
      (node (ref "RN1") (pin "4") (pinfunction "1_4") (pintype "passive"))
    )
    (net (code "51") (name "Net-(IC4-TOCAP)") (class "Default")
      (node (ref "C16") (pin "1") (pinfunction "1_1") (pintype "passive"))
      (node (ref "IC4") (pin "20") (pinfunction "TOCAP_20") (pintype "passive"))
    )
    (net (code "52") (name "Net-(IC4-XI{slash}CLKIN)") (class "Default")
      (node (ref "C1") (pin "1") (pinfunction "1_1") (pintype "passive"))
      (node (ref "IC4") (pin "30") (pinfunction "XI/CLKIN_30") (pintype "passive"))
      (node (ref "R31") (pin "2") (pinfunction "2_2") (pintype "passive"))
      (node (ref "XTL1") (pin "1") (pinfunction "1_1") (pintype "passive"))
    )
    (net (code "53") (name "Net-(IC4-XO)") (class "Default")
      (node (ref "C2") (pin "1") (pinfunction "1_1") (pintype "passive"))
      (node (ref "IC4") (pin "31") (pinfunction "XO_31") (pintype "passive"))
      (node (ref "R31") (pin "1") (pinfunction "1_1") (pintype "passive"))
      (node (ref "XTL1") (pin "3") (pinfunction "2_3") (pintype "passive"))
    )
    (net (code "54") (name "Net-(IC5-VBUS)") (class "Default")
      (node (ref "IC5") (pin "8") (pinfunction "VBUS_8") (pintype "bidirectional"))
      (node (ref "R29") (pin "1") (pinfunction "1_1") (pintype "passive"))
      (node (ref "R30") (pin "2") (pinfunction "2_2") (pintype "passive"))
    )
    (net (code "55") (name "Net-(J3-CC1)") (class "Default")
      (node (ref "J3") (pin "A5") (pinfunction "CC1_A5") (pintype "bidirectional"))
      (node (ref "R18") (pin "2") (pinfunction "2_2") (pintype "passive"))
    )
    (net (code "56") (name "Net-(J3-CC2)") (class "Default")
      (node (ref "J3") (pin "B5") (pinfunction "CC2_B5") (pintype "bidirectional"))
      (node (ref "R19") (pin "2") (pinfunction "2_2") (pintype "passive"))
    )
    (net (code "57") (name "Net-(J5-Pad1)") (class "Default")
      (node (ref "J5") (pin "1") (pinfunction "1_1") (pintype "passive"))
      (node (ref "R16") (pin "1") (pinfunction "1_1") (pintype "passive"))
    )
    (net (code "58") (name "Net-(J6-Pad1)") (class "Default")
      (node (ref "J6") (pin "1") (pinfunction "1_1") (pintype "passive"))
      (node (ref "R14") (pin "1") (pinfunction "1_1") (pintype "passive"))
    )
    (net (code "59") (name "Net-(J7-Pad2)") (class "Default")
      (node (ref "J7") (pin "2") (pinfunction "2_2") (pintype "passive"))
      (node (ref "R17") (pin "1") (pinfunction "1_1") (pintype "passive"))
    )
    (net (code "60") (name "Net-(LED1-PadC)") (class "Default")
      (node (ref "LED1") (pin "C") (pinfunction "C_C") (pintype "passive"))
      (node (ref "R9") (pin "2") (pinfunction "2_2") (pintype "passive"))
    )
    (net (code "61") (name "Net-(LED2-PadC)") (class "Default")
      (node (ref "LED2") (pin "C") (pinfunction "C_C") (pintype "passive"))
      (node (ref "R8") (pin "2") (pinfunction "2_2") (pintype "passive"))
    )
    (net (code "62") (name "Net-(LED3-PadC)") (class "Default")
      (node (ref "LED3") (pin "C") (pinfunction "C_C") (pintype "passive"))
      (node (ref "R11") (pin "2") (pinfunction "2_2") (pintype "passive"))
    )
    (net (code "63") (name "Net-(LED4-PadC)") (class "Default")
      (node (ref "LED4") (pin "C") (pinfunction "C_C") (pintype "passive"))
      (node (ref "R10") (pin "2") (pinfunction "2_2") (pintype "passive"))
    )
    (net (code "64") (name "Net-(LED5-PadC)") (class "Default")
      (node (ref "LED5") (pin "C") (pinfunction "C_C") (pintype "passive"))
      (node (ref "R6") (pin "2") (pinfunction "2_2") (pintype "passive"))
    )
    (net (code "65") (name "Net-(LED6-PadC)") (class "Default")
      (node (ref "LED6") (pin "C") (pinfunction "C_C") (pintype "passive"))
      (node (ref "R7") (pin "2") (pinfunction "2_2") (pintype "passive"))
    )
    (net (code "66") (name "Net-(LED7-PadA)") (class "Default")
      (node (ref "LED7") (pin "A") (pinfunction "A_A") (pintype "passive"))
      (node (ref "R15") (pin "1") (pinfunction "1_1") (pintype "passive"))
    )
    (net (code "67") (name "Net-(Q2A-B)") (class "Default")
      (node (ref "Q2") (pin "5") (pinfunction "B_5") (pintype "passive"))
      (node (ref "R24") (pin "2") (pinfunction "2_2") (pintype "passive"))
    )
    (net (code "68") (name "Net-(Q2B-B)") (class "Default")
      (node (ref "Q2") (pin "2") (pinfunction "B_2") (pintype "passive"))
      (node (ref "R25") (pin "2") (pinfunction "2_2") (pintype "passive"))
    )
    (net (code "69") (name "Net-(U1-G-)") (class "Default")
      (node (ref "R12") (pin "1") (pinfunction "1_1") (pintype "passive"))
      (node (ref "U1") (pin "P$14") (pinfunction "G-_P$14") (pintype "bidirectional"))
    )
    (net (code "70") (name "Net-(U1-RXCT)") (class "Default")
      (node (ref "C5") (pin "1") (pinfunction "1_1") (pintype "passive"))
      (node (ref "R3") (pin "1") (pinfunction "1_1") (pintype "passive"))
      (node (ref "R4") (pin "1") (pinfunction "1_1") (pintype "passive"))
      (node (ref "U1") (pin "P$3") (pinfunction "RXCT_P$3") (pintype "bidirectional"))
    )
    (net (code "71") (name "Net-(U1-TXCT)") (class "Default")
      (node (ref "C6") (pin "1") (pinfunction "1_1") (pintype "passive"))
      (node (ref "R1") (pin "2") (pinfunction "2_2") (pintype "passive"))
      (node (ref "U1") (pin "P$4") (pinfunction "TXCT_P$4") (pintype "bidirectional"))
    )
    (net (code "72") (name "Net-(U1-Y-)") (class "Default")
      (node (ref "R13") (pin "1") (pinfunction "1_1") (pintype "passive"))
      (node (ref "U1") (pin "P$12") (pinfunction "Y-_P$12") (pintype "bidirectional"))
    )
    (net (code "73") (name "Net-(VR2-VOUT)") (class "Default")
      (node (ref "D2") (pin "A") (pinfunction "A_A") (pintype "passive"))
      (node (ref "J8") (pin "2") (pinfunction "2_2") (pintype "passive"))
      (node (ref "VR2") (pin "6") (pinfunction "VOUT_6") (pintype "bidirectional"))
    )
    (net (code "74") (name "POEV+") (class "Default")
      (node (ref "J8") (pin "1") (pinfunction "1_1") (pintype "passive"))
      (node (ref "U1") (pin "P$9") (pinfunction "V+_P$9") (pintype "bidirectional"))
      (node (ref "VR2") (pin "1") (pinfunction "VA1_1") (pintype "power_in"))
    )
    (net (code "75") (name "POEV-") (class "Default")
      (node (ref "J9") (pin "1") (pinfunction "1_1") (pintype "passive"))
      (node (ref "U1") (pin "P$10") (pinfunction "V-_P$10") (pintype "bidirectional"))
      (node (ref "VR2") (pin "2") (pinfunction "VA2_2") (pintype "power_in"))
    )
    (net (code "76") (name "RTS") (class "Default")
      (node (ref "IC5") (pin "19") (pinfunction "RTS_19") (pintype "output"))
      (node (ref "Q2") (pin "4") (pinfunction "E_4") (pintype "passive"))
      (node (ref "R25") (pin "1") (pinfunction "1_1") (pintype "passive"))
    )
    (net (code "77") (name "RXD0") (class "Default")
      (node (ref "IC2") (pin "34") (pinfunction "RXD0_34") (pintype "bidirectional"))
      (node (ref "IC5") (pin "21") (pinfunction "TXD_21") (pintype "output"))
    )
    (net (code "78") (name "RXIN") (class "Default")
      (node (ref "IC4") (pin "5") (pinfunction "RXIN_5") (pintype "passive"))
      (node (ref "R4") (pin "2") (pinfunction "2_2") (pintype "passive"))
      (node (ref "U1") (pin "P$2") (pinfunction "RX-_P$2") (pintype "bidirectional"))
    )
    (net (code "79") (name "RXIP") (class "Default")
      (node (ref "IC4") (pin "6") (pinfunction "RXIP_6") (pintype "passive"))
      (node (ref "R3") (pin "2") (pinfunction "2_2") (pintype "passive"))
      (node (ref "U1") (pin "P$1") (pinfunction "RX+_P$1") (pintype "bidirectional"))
    )
    (net (code "80") (name "RX_LED") (class "Default")
      (node (ref "IC5") (pin "13") (pinfunction "GPIO_1_13") (pintype "bidirectional"))
      (node (ref "R10") (pin "1") (pinfunction "1_1") (pintype "passive"))
    )
    (net (code "81") (name "SPDLED") (class "Default")
      (node (ref "IC4") (pin "24") (pinfunction "~{SPD}_24") (pintype "passive"))
      (node (ref "R7") (pin "1") (pinfunction "1_1") (pintype "passive"))
    )
    (net (code "82") (name "TXD0") (class "Default")
      (node (ref "IC2") (pin "35") (pinfunction "TXD0_35") (pintype "bidirectional"))
      (node (ref "IC5") (pin "20") (pinfunction "RXD_20") (pintype "input"))
    )
    (net (code "83") (name "TXON") (class "Default")
      (node (ref "IC4") (pin "1") (pinfunction "TXON_1") (pintype "passive"))
      (node (ref "R2") (pin "1") (pinfunction "1_1") (pintype "passive"))
      (node (ref "U1") (pin "P$6") (pinfunction "TX-_P$6") (pintype "bidirectional"))
    )
    (net (code "84") (name "TXOP") (class "Default")
      (node (ref "IC4") (pin "2") (pinfunction "TXOP_2") (pintype "passive"))
      (node (ref "R5") (pin "1") (pinfunction "1_1") (pintype "passive"))
      (node (ref "U1") (pin "P$5") (pinfunction "TX+_P$5") (pintype "bidirectional"))
    )
    (net (code "85") (name "TX_LED") (class "Default")
      (node (ref "IC5") (pin "14") (pinfunction "GPIO_0_14") (pintype "bidirectional"))
      (node (ref "R11") (pin "1") (pinfunction "1_1") (pintype "passive"))
    )
    (net (code "86") (name "USBVCC") (class "Default")
      (node (ref "F1") (pin "2") (pinfunction "2_2") (pintype "passive"))
      (node (ref "Q1") (pin "3") (pinfunction "D_3") (pintype "passive"))
    )
    (net (code "87") (name "VB1") (class "Default")
      (node (ref "VR2") (pin "3") (pinfunction "VB1_3") (pintype "power_in"))
    )
    (net (code "88") (name "VB2") (class "Default")
      (node (ref "VR2") (pin "4") (pinfunction "VB2_4") (pintype "power_in"))
    )
    (net (code "89") (name "unconnected-(IC1-ALERT-Pad3)") (class "Default")
      (node (ref "IC1") (pin "3") (pinfunction "ALERT_3") (pintype "bidirectional"))
    )
    (net (code "90") (name "unconnected-(IC2-CLK-Pad20)") (class "Default")
      (node (ref "IC2") (pin "20") (pinfunction "CLK_20") (pintype "bidirectional"))
    )
    (net (code "91") (name "unconnected-(IC2-CMD-Pad19)") (class "Default")
      (node (ref "IC2") (pin "19") (pinfunction "CMD_19") (pintype "bidirectional"))
    )
    (net (code "92") (name "unconnected-(IC2-IO15-Pad23)") (class "Default")
      (node (ref "IC2") (pin "23") (pinfunction "IO15_23") (pintype "bidirectional"))
    )
    (net (code "93") (name "unconnected-(IC2-NC-Pad32)") (class "Default")
      (node (ref "IC2") (pin "32") (pinfunction "NC_32") (pintype "bidirectional"))
    )
    (net (code "94") (name "unconnected-(IC2-SD0-Pad21)") (class "Default")
      (node (ref "IC2") (pin "21") (pinfunction "SD0_21") (pintype "bidirectional"))
    )
    (net (code "95") (name "unconnected-(IC2-SD1-Pad22)") (class "Default")
      (node (ref "IC2") (pin "22") (pinfunction "SD1_22") (pintype "bidirectional"))
    )
    (net (code "96") (name "unconnected-(IC2-SD2-Pad17)") (class "Default")
      (node (ref "IC2") (pin "17") (pinfunction "SD2_17") (pintype "bidirectional"))
    )
    (net (code "97") (name "unconnected-(IC2-SD3-Pad18)") (class "Default")
      (node (ref "IC2") (pin "18") (pinfunction "SD3_18") (pintype "bidirectional"))
    )
    (net (code "98") (name "unconnected-(IC4-DNC-Pad7)") (class "Default")
      (node (ref "IC4") (pin "7") (pinfunction "DNC_7") (pintype "passive"))
    )
    (net (code "99") (name "unconnected-(IC4-NC-Pad12)") (class "Default")
      (node (ref "IC4") (pin "12") (pinfunction "NC_12") (pintype "passive"))
    )
    (net (code "100") (name "unconnected-(IC4-NC-Pad13)") (class "Default")
      (node (ref "IC4") (pin "13") (pinfunction "NC_13") (pintype "passive"))
    )
    (net (code "101") (name "unconnected-(IC4-NC-Pad46)") (class "Default")
      (node (ref "IC4") (pin "46") (pinfunction "NC_46") (pintype "passive"))
    )
    (net (code "102") (name "unconnected-(IC4-NC-Pad47)") (class "Default")
      (node (ref "IC4") (pin "47") (pinfunction "NC_47") (pintype "passive"))
    )
    (net (code "103") (name "unconnected-(IC4-VBG-Pad18)") (class "Default")
      (node (ref "IC4") (pin "18") (pinfunction "VBG_18") (pintype "passive"))
    )
    (net (code "104") (name "unconnected-(IC5-CTS-Pad18)") (class "Default")
      (node (ref "IC5") (pin "18") (pinfunction "CTS_18") (pintype "input"))
    )
    (net (code "105") (name "unconnected-(IC5-DCD-Pad24)") (class "Default")
      (node (ref "IC5") (pin "24") (pinfunction "DCD_24") (pintype "input"))
    )
    (net (code "106") (name "unconnected-(IC5-DSR-Pad22)") (class "Default")
      (node (ref "IC5") (pin "22") (pinfunction "DSR_22") (pintype "input"))
    )
    (net (code "107") (name "unconnected-(IC5-GPIO_2-Pad12)") (class "Default")
      (node (ref "IC5") (pin "12") (pinfunction "GPIO_2_12") (pintype "bidirectional"))
    )
    (net (code "108") (name "unconnected-(IC5-GPIO_3-Pad11)") (class "Default")
      (node (ref "IC5") (pin "11") (pinfunction "GPIO_3_11") (pintype "bidirectional"))
    )
    (net (code "109") (name "unconnected-(IC5-NC-Pad10)") (class "Default")
      (node (ref "IC5") (pin "10") (pinfunction "NC_10") (pintype "input"))
    )
    (net (code "110") (name "unconnected-(IC5-RI-Pad1)") (class "Default")
      (node (ref "IC5") (pin "1") (pinfunction "RI_1") (pintype "input"))
    )
    (net (code "111") (name "unconnected-(IC5-SUSPEND-Pad17)") (class "Default")
      (node (ref "IC5") (pin "17") (pinfunction "SUSPEND_17") (pintype "output"))
    )
    (net (code "112") (name "unconnected-(IC5-VPP-Pad16)") (class "Default")
      (node (ref "IC5") (pin "16") (pinfunction "VPP_16") (pintype "bidirectional"))
    )
    (net (code "113") (name "unconnected-(IC5-~{RST}-Pad9)") (class "Default")
      (node (ref "IC5") (pin "9") (pinfunction "~{RST}_9") (pintype "bidirectional"))
    )
    (net (code "114") (name "unconnected-(IC5-~{SUSPEND}-Pad15)") (class "Default")
      (node (ref "IC5") (pin "15") (pinfunction "~{SUSPEND}_15") (pintype "output"))
    )
    (net (code "115") (name "unconnected-(J3-SBU1-PadA8)") (class "Default")
      (node (ref "J3") (pin "A8") (pinfunction "SBU1_A8") (pintype "bidirectional"))
    )
    (net (code "116") (name "unconnected-(J3-SBU2-PadB8)") (class "Default")
      (node (ref "J3") (pin "B8") (pinfunction "SBU2_B8") (pintype "bidirectional"))
    )
    (net (code "117") (name "unconnected-(J10-NC-Pad1)") (class "Default")
      (node (ref "J10") (pin "1") (pinfunction "NC_1") (pintype "bidirectional"))
    )
    (net (code "118") (name "unconnected-(J10-PadCD1)") (class "Default")
      (node (ref "J10") (pin "CD1") (pinfunction "CD1_CD1") (pintype "bidirectional"))
    )
    (net (code "119") (name "unconnected-(J10-RSV-Pad8)") (class "Default")
      (node (ref "J10") (pin "8") (pinfunction "RSV_8") (pintype "bidirectional"))
    )
    (net (code "120") (name "unconnected-(VR3-NC-Pad4)") (class "Default")
      (node (ref "VR3") (pin "4") (pinfunction "NC_4") (pintype "bidirectional"))
    )
    (net (code "121") (name "~{RESET}") (class "Default")
      (node (ref "C15") (pin "1") (pinfunction "1_1") (pintype "passive"))
      (node (ref "IC2") (pin "3") (pinfunction "EN_3") (pintype "bidirectional"))
      (node (ref "J2") (pin "6") (pinfunction "6_6") (pintype "passive"))
      (node (ref "Q2") (pin "3") (pinfunction "C_3") (pintype "passive"))
      (node (ref "R27") (pin "2") (pinfunction "2_2") (pintype "passive"))
      (node (ref "S1") (pin "2") (pinfunction "S_2") (pintype "passive"))
    )
  )
)
